# Buoy3.net
KiCad netlist of a schematic drawn in EAGLE
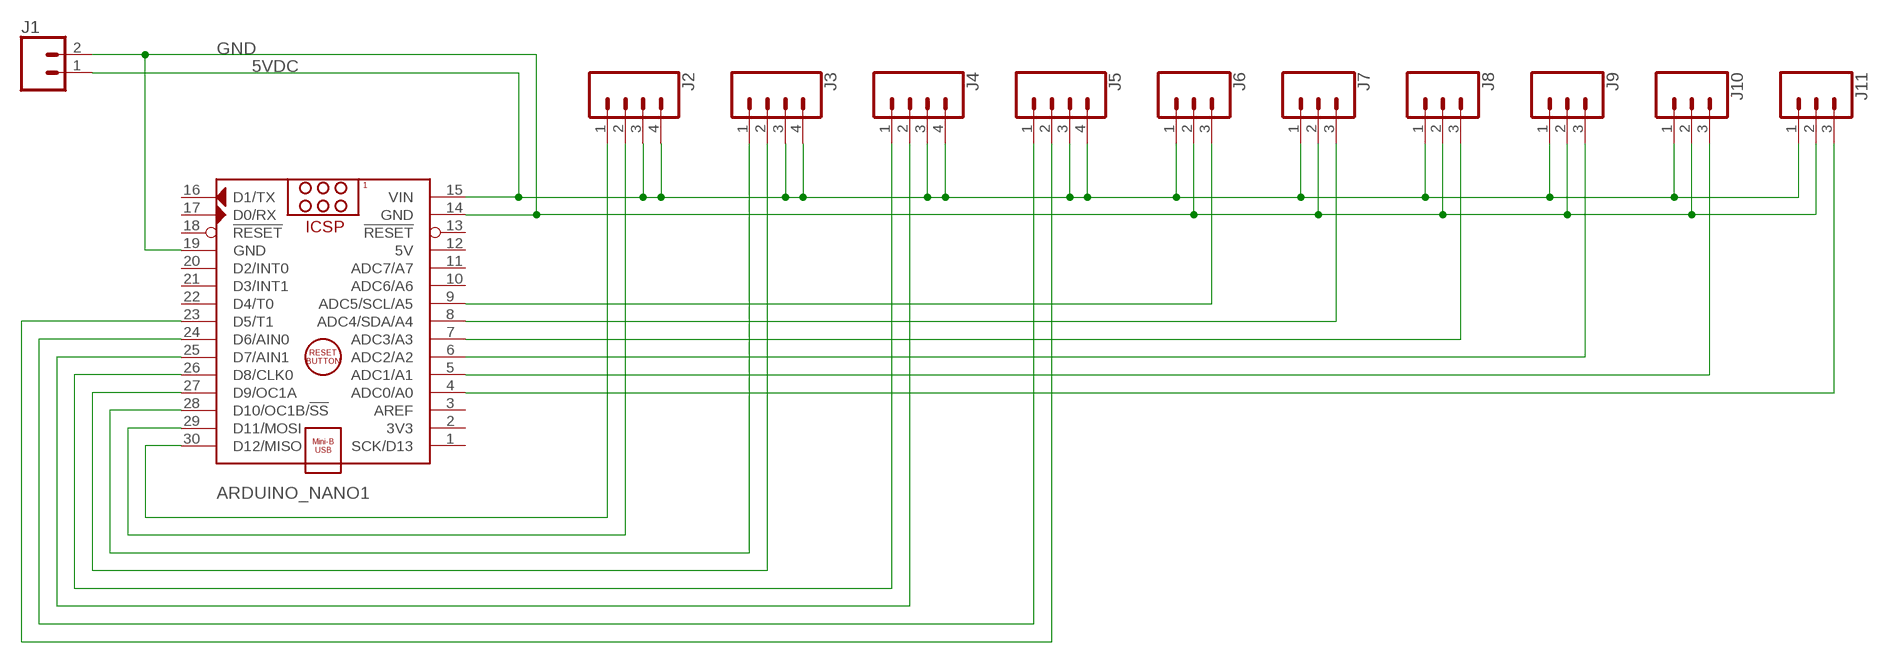
[diagram p0: schematic, sheet 1]

(export (version "E")
  (design (tool "Eeschema 10.0.6"))
  (components
    (comp (ref "ARDUINO_NANO1")
      (value "ARDUINO_NANO")
      (footprint "eagle-import:ARDUINO_NANO")
      (libsource (lib "eagle-import") (part "ARDUINO_NANO"))
    )
    (comp (ref "J1")
      (value "CONN_023.5MM_LOCK")
      (footprint "eagle-import:SCREWTERMINAL-3.5MM-2_LOCK")
      (libsource (lib "eagle-import") (part "CONN_023.5MM_LOCK"))
    )
    (comp (ref "J2")
      (value "CONN_04SCREW")
      (footprint "eagle-import:SCREWTERMINAL-3.5MM-4")
      (libsource (lib "eagle-import") (part "CONN_04SCREW"))
    )
    (comp (ref "J3")
      (value "CONN_04SCREW")
      (footprint "eagle-import:SCREWTERMINAL-3.5MM-4")
      (libsource (lib "eagle-import") (part "CONN_04SCREW"))
    )
    (comp (ref "J4")
      (value "CONN_04SCREW")
      (footprint "eagle-import:SCREWTERMINAL-3.5MM-4")
      (libsource (lib "eagle-import") (part "CONN_04SCREW"))
    )
    (comp (ref "J5")
      (value "CONN_04SCREW")
      (footprint "eagle-import:SCREWTERMINAL-3.5MM-4")
      (libsource (lib "eagle-import") (part "CONN_04SCREW"))
    )
    (comp (ref "J6")
      (value "CONN_03SCREW_LOCK")
      (footprint "eagle-import:SCREWTERMINAL-3.5MM-3_LOCK.007S")
      (libsource (lib "eagle-import") (part "CONN_03SCREW_LOCK"))
    )
    (comp (ref "J7")
      (value "CONN_03SCREW_LOCK")
      (footprint "eagle-import:SCREWTERMINAL-3.5MM-3_LOCK.007S")
      (libsource (lib "eagle-import") (part "CONN_03SCREW_LOCK"))
    )
    (comp (ref "J8")
      (value "CONN_03SCREW_LOCK")
      (footprint "eagle-import:SCREWTERMINAL-3.5MM-3_LOCK.007S")
      (libsource (lib "eagle-import") (part "CONN_03SCREW_LOCK"))
    )
    (comp (ref "J9")
      (value "CONN_03SCREW_LOCK")
      (footprint "eagle-import:SCREWTERMINAL-3.5MM-3_LOCK.007S")
      (libsource (lib "eagle-import") (part "CONN_03SCREW_LOCK"))
    )
    (comp (ref "J10")
      (value "CONN_03SCREW_LOCK")
      (footprint "eagle-import:SCREWTERMINAL-3.5MM-3_LOCK.007S")
      (libsource (lib "eagle-import") (part "CONN_03SCREW_LOCK"))
    )
    (comp (ref "J11")
      (value "CONN_03SCREW_LOCK")
      (footprint "eagle-import:SCREWTERMINAL-3.5MM-3_LOCK.007S")
      (libsource (lib "eagle-import") (part "CONN_03SCREW_LOCK"))
    )
  )
  (nets
    (net (code "1") (name "/5V") (class "Default")
      (node (ref "ARDUINO_NANO1") (pin "12") (pinfunction "5V_12") (pintype "power_in"))
    )
    (net (code "2") (name "/5VDC") (class "Default")
      (node (ref "ARDUINO_NANO1") (pin "15") (pinfunction "VIN_15") (pintype "power_in"))
      (node (ref "J1") (pin "1") (pinfunction "1_1") (pintype "passive"))
      (node (ref "J10") (pin "1") (pinfunction "1_1") (pintype "passive"))
      (node (ref "J11") (pin "1") (pinfunction "1_1") (pintype "passive"))
      (node (ref "J2") (pin "3") (pinfunction "3_3") (pintype "passive"))
      (node (ref "J2") (pin "4") (pinfunction "4_4") (pintype "passive"))
      (node (ref "J3") (pin "3") (pinfunction "3_3") (pintype "passive"))
      (node (ref "J3") (pin "4") (pinfunction "4_4") (pintype "passive"))
      (node (ref "J4") (pin "3") (pinfunction "3_3") (pintype "passive"))
      (node (ref "J4") (pin "4") (pinfunction "4_4") (pintype "passive"))
      (node (ref "J5") (pin "3") (pinfunction "3_3") (pintype "passive"))
      (node (ref "J5") (pin "4") (pinfunction "4_4") (pintype "passive"))
      (node (ref "J6") (pin "1") (pinfunction "1_1") (pintype "passive"))
      (node (ref "J7") (pin "1") (pinfunction "1_1") (pintype "passive"))
      (node (ref "J8") (pin "1") (pinfunction "1_1") (pintype "passive"))
      (node (ref "J9") (pin "1") (pinfunction "1_1") (pintype "passive"))
    )
    (net (code "3") (name "/GND") (class "Default")
      (node (ref "ARDUINO_NANO1") (pin "14") (pinfunction "GND_14") (pintype "power_in"))
      (node (ref "ARDUINO_NANO1") (pin "19") (pinfunction "GND_19") (pintype "power_in"))
      (node (ref "J1") (pin "2") (pinfunction "2_2") (pintype "passive"))
      (node (ref "J10") (pin "2") (pinfunction "2_2") (pintype "passive"))
      (node (ref "J11") (pin "2") (pinfunction "2_2") (pintype "passive"))
      (node (ref "J6") (pin "2") (pinfunction "2_2") (pintype "passive"))
      (node (ref "J7") (pin "2") (pinfunction "2_2") (pintype "passive"))
      (node (ref "J8") (pin "2") (pinfunction "2_2") (pintype "passive"))
      (node (ref "J9") (pin "2") (pinfunction "2_2") (pintype "passive"))
    )
    (net (code "4") (name "Net-(ARDUINO_NANO1-ADC0{slash}A0)") (class "Default")
      (node (ref "ARDUINO_NANO1") (pin "4") (pinfunction "ADC0/A0_4") (pintype "bidirectional"))
      (node (ref "J11") (pin "3") (pinfunction "3_3") (pintype "passive"))
    )
    (net (code "5") (name "Net-(ARDUINO_NANO1-ADC1{slash}A1)") (class "Default")
      (node (ref "ARDUINO_NANO1") (pin "5") (pinfunction "ADC1/A1_5") (pintype "bidirectional"))
      (node (ref "J10") (pin "3") (pinfunction "3_3") (pintype "passive"))
    )
    (net (code "6") (name "Net-(ARDUINO_NANO1-ADC2{slash}A2)") (class "Default")
      (node (ref "ARDUINO_NANO1") (pin "6") (pinfunction "ADC2/A2_6") (pintype "bidirectional"))
      (node (ref "J9") (pin "3") (pinfunction "3_3") (pintype "passive"))
    )
    (net (code "7") (name "Net-(ARDUINO_NANO1-ADC3{slash}A3)") (class "Default")
      (node (ref "ARDUINO_NANO1") (pin "7") (pinfunction "ADC3/A3_7") (pintype "bidirectional"))
      (node (ref "J8") (pin "3") (pinfunction "3_3") (pintype "passive"))
    )
    (net (code "8") (name "Net-(ARDUINO_NANO1-ADC4{slash}SDA{slash}A4)") (class "Default")
      (node (ref "ARDUINO_NANO1") (pin "8") (pinfunction "ADC4/SDA/A4_8") (pintype "bidirectional"))
      (node (ref "J7") (pin "3") (pinfunction "3_3") (pintype "passive"))
    )
    (net (code "9") (name "Net-(ARDUINO_NANO1-ADC5{slash}SCL{slash}A5)") (class "Default")
      (node (ref "ARDUINO_NANO1") (pin "9") (pinfunction "ADC5/SCL/A5_9") (pintype "bidirectional"))
      (node (ref "J6") (pin "3") (pinfunction "3_3") (pintype "passive"))
    )
    (net (code "10") (name "Net-(ARDUINO_NANO1-D5{slash}T1)") (class "Default")
      (node (ref "ARDUINO_NANO1") (pin "23") (pinfunction "D5/T1_23") (pintype "bidirectional"))
      (node (ref "J5") (pin "2") (pinfunction "2_2") (pintype "passive"))
    )
    (net (code "11") (name "Net-(ARDUINO_NANO1-D6{slash}AIN0)") (class "Default")
      (node (ref "ARDUINO_NANO1") (pin "24") (pinfunction "D6/AIN0_24") (pintype "bidirectional"))
      (node (ref "J5") (pin "1") (pinfunction "1_1") (pintype "passive"))
    )
    (net (code "12") (name "Net-(ARDUINO_NANO1-D7{slash}AIN1)") (class "Default")
      (node (ref "ARDUINO_NANO1") (pin "25") (pinfunction "D7/AIN1_25") (pintype "bidirectional"))
      (node (ref "J4") (pin "2") (pinfunction "2_2") (pintype "passive"))
    )
    (net (code "13") (name "Net-(ARDUINO_NANO1-D8{slash}CLK0)") (class "Default")
      (node (ref "ARDUINO_NANO1") (pin "26") (pinfunction "D8/CLK0_26") (pintype "bidirectional"))
      (node (ref "J4") (pin "1") (pinfunction "1_1") (pintype "passive"))
    )
    (net (code "14") (name "Net-(ARDUINO_NANO1-D9{slash}OC1A)") (class "Default")
      (node (ref "ARDUINO_NANO1") (pin "27") (pinfunction "D9/OC1A_27") (pintype "bidirectional"))
      (node (ref "J3") (pin "2") (pinfunction "2_2") (pintype "passive"))
    )
    (net (code "15") (name "Net-(ARDUINO_NANO1-D10{slash}OC1B{slash}~{SS})") (class "Default")
      (node (ref "ARDUINO_NANO1") (pin "28") (pinfunction "D10/OC1B/~{SS}_28") (pintype "bidirectional"))
      (node (ref "J3") (pin "1") (pinfunction "1_1") (pintype "passive"))
    )
    (net (code "16") (name "Net-(ARDUINO_NANO1-D11{slash}MOSI)") (class "Default")
      (node (ref "ARDUINO_NANO1") (pin "29") (pinfunction "D11/MOSI_29") (pintype "bidirectional"))
      (node (ref "J2") (pin "2") (pinfunction "2_2") (pintype "passive"))
    )
    (net (code "17") (name "Net-(ARDUINO_NANO1-D12{slash}MISO)") (class "Default")
      (node (ref "ARDUINO_NANO1") (pin "30") (pinfunction "D12/MISO_30") (pintype "bidirectional"))
      (node (ref "J2") (pin "1") (pinfunction "1_1") (pintype "passive"))
    )
    (net (code "18") (name "unconnected-(ARDUINO_NANO1-3V3-Pad2)") (class "Default")
      (node (ref "ARDUINO_NANO1") (pin "2") (pinfunction "3V3_2") (pintype "output"))
    )
    (net (code "19") (name "unconnected-(ARDUINO_NANO1-ADC6{slash}A6-Pad10)") (class "Default")
      (node (ref "ARDUINO_NANO1") (pin "10") (pinfunction "ADC6/A6_10") (pintype "bidirectional"))
    )
    (net (code "20") (name "unconnected-(ARDUINO_NANO1-ADC7{slash}A7-Pad11)") (class "Default")
      (node (ref "ARDUINO_NANO1") (pin "11") (pinfunction "ADC7/A7_11") (pintype "bidirectional"))
    )
    (net (code "21") (name "unconnected-(ARDUINO_NANO1-AREF-Pad3)") (class "Default")
      (node (ref "ARDUINO_NANO1") (pin "3") (pinfunction "AREF_3") (pintype "input"))
    )
    (net (code "22") (name "unconnected-(ARDUINO_NANO1-D0{slash}RX-Pad17)") (class "Default")
      (node (ref "ARDUINO_NANO1") (pin "17") (pinfunction "D0/RX_17") (pintype "bidirectional"))
    )
    (net (code "23") (name "unconnected-(ARDUINO_NANO1-D1{slash}TX-Pad16)") (class "Default")
      (node (ref "ARDUINO_NANO1") (pin "16") (pinfunction "D1/TX_16") (pintype "bidirectional"))
    )
    (net (code "24") (name "unconnected-(ARDUINO_NANO1-D2{slash}INT0-Pad20)") (class "Default")
      (node (ref "ARDUINO_NANO1") (pin "20") (pinfunction "D2/INT0_20") (pintype "bidirectional"))
    )
    (net (code "25") (name "unconnected-(ARDUINO_NANO1-D3{slash}INT1-Pad21)") (class "Default")
      (node (ref "ARDUINO_NANO1") (pin "21") (pinfunction "D3/INT1_21") (pintype "bidirectional"))
    )
    (net (code "26") (name "unconnected-(ARDUINO_NANO1-D4{slash}T0-Pad22)") (class "Default")
      (node (ref "ARDUINO_NANO1") (pin "22") (pinfunction "D4/T0_22") (pintype "bidirectional"))
    )
    (net (code "27") (name "unconnected-(ARDUINO_NANO1-SCK{slash}D13-Pad1)") (class "Default")
      (node (ref "ARDUINO_NANO1") (pin "1") (pinfunction "SCK/D13_1") (pintype "bidirectional"))
    )
    (net (code "28") (name "unconnected-(ARDUINO_NANO1-~{RESET}-Pad13)") (class "Default")
      (node (ref "ARDUINO_NANO1") (pin "13") (pinfunction "~{RESET}_13") (pintype "input"))
    )
    (net (code "29") (name "unconnected-(ARDUINO_NANO1-~{RESET}-Pad18)") (class "Default")
      (node (ref "ARDUINO_NANO1") (pin "18") (pinfunction "~{RESET}_18") (pintype "input"))
    )
  )
)
